# 5_Motor_Driver_Schematic.net
KiCad netlist of a schematic drawn in Altium Designer
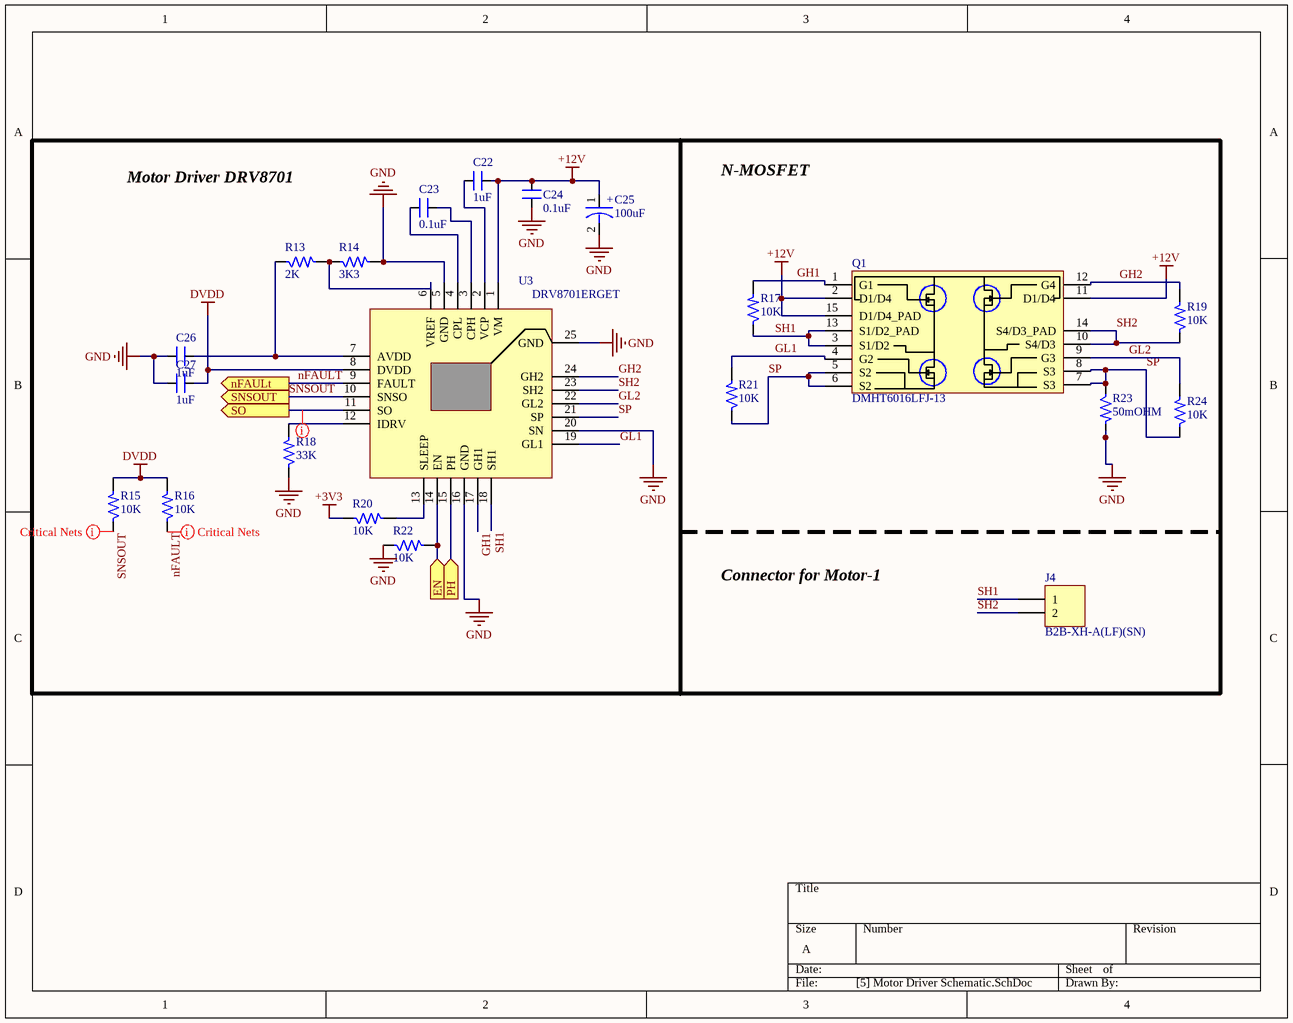
[diagram p0: [5] Motor Driver Schematic.SchDoc]

(export (version "E")
  (design (tool "Eeschema 10.0.6"))
  (components
    (comp (ref "C22")
      (value "1uF")
      (footprint "CAP_0805")
      (description "1µF ±5% 50V Ceramic Capacitor X7R 0805 (2012 Metric)")
      (fields
        (field (name "MANUFACTURER") "Samsung")
        (field (name "MANUFACTURER PART NUMBER") "CC0805JKX7R9BB105")
      )
      (libsource (lib "ESTEEMPCBLIB") (part "CAP_1uF-50V-5%-0805"))
    )
    (comp (ref "C23")
      (value "0.1uF")
      (footprint "CAP_0805")
      (description "0.1µF ±10% 50V Ceramic Capacitor X7R 0805 (2012 Metric)")
      (fields
        (field (name "MANUFACTURER") "Samsung")
        (field (name "MANUFACTURER PART NUMBER") "CL21B104KBCNNNC")
      )
      (libsource (lib "ESTEEMPCBLIB") (part "CAP_0.1uF-50V-10%-0805"))
    )
    (comp (ref "C24")
      (value "0.1uF")
      (footprint "CAP_0805")
      (description "0.1µF ±10% 50V Ceramic Capacitor X7R 0805 (2012 Metric)")
      (fields
        (field (name "MANUFACTURER") "Samsung")
        (field (name "MANUFACTURER PART NUMBER") "CL21B104KBCNNNC")
      )
      (libsource (lib "ESTEEMPCBLIB") (part "CAP_0.1uF-50V-10%-0805"))
    )
    (comp (ref "C25")
      (value "100uF")
      (footprint "ACAP_P236_D305_H303_RAD")
      (description "100µF 25V Aluminum Electrolytic Capacitors Radial, Can - SMD 1000 Hrs @ 105°C")
      (fields
        (field (name "MANUFACTURER") "Nichicon")
        (field (name "MANUFACTURER PART NUMBER") "UWT1E101MCL1GS")
      )
      (libsource (lib "ESTEEMPCBLIB") (part "CAP-P_100uF-25V-20%-RAD"))
    )
    (comp (ref "C26")
      (value "1uF")
      (footprint "CAP_0805")
      (description "1µF ±5% 50V Ceramic Capacitor X7R 0805 (2012 Metric)")
      (fields
        (field (name "MANUFACTURER") "Samsung")
        (field (name "MANUFACTURER PART NUMBER") "CC0805JKX7R9BB105")
      )
      (libsource (lib "ESTEEMPCBLIB") (part "CAP_1uF-50V-5%-0805"))
    )
    (comp (ref "C27")
      (value "1uF")
      (footprint "CAP_0805")
      (description "1µF ±5% 50V Ceramic Capacitor X7R 0805 (2012 Metric)")
      (fields
        (field (name "MANUFACTURER") "Samsung")
        (field (name "MANUFACTURER PART NUMBER") "CC0805JKX7R9BB105")
      )
      (libsource (lib "ESTEEMPCBLIB") (part "CAP_1uF-50V-5%-0805"))
    )
    (comp (ref "J4")
      (value "B2B-XH-A(LF)(SN)")
      (footprint "CON2_100_B2B-XH-A_TH_ST")
      (description "2 Pins, 1 Row 2.54mm Pitch, Straight Connector, male")
      (fields (field (name "MANUFACTURER") "JST") (field (name "MATING PART NUMBER") "XHP-2"))
      (libsource (lib "ESTEEMPCBLIB") (part "CON-PLG_2X1-100-ST-TH"))
    )
    (comp (ref "Q1")
      (value "DMHT6016LFJ-13")
      (footprint "DFN5045-12_33_212_27X15_SMD_1")
      (description "Mosfet Array 4 N-Channel 14.8A (Ta) Surface Mount V-DFN5045-12")
      (fields (field (name "MANUFACTURER") "ON Semiconductor"))
      (libsource (lib "ESTEEMPCBLIB") (part "MOSFET-N_60V-14.8A-V-DFN5045-12"))
    )
    (comp (ref "R13")
      (value "2K")
      (footprint "RES_0603")
      (fields
        (field (name "MANUFACTURER") "Stackpole Electronics")
        (field (name "MANUFACTURER PART NUMBER") "RNCP0603FTD2K00")
      )
      (libsource (lib "ESTEEMPCBLIB") (part "RES_2K-0.125W-1%-0603"))
    )
    (comp (ref "R14")
      (value "3K3")
      (footprint "RES_0603")
      (description "3.3 kOhms ±1% 0.1W, 1/10W Chip Resistor 0603 (1608 Metric) Automotive AEC-Q200 Thick Film")
      (fields (field (name "MANUFACTURER") "Wilson") (field (name "MANUFACTURER PART NUMBER") "WR06X3301FTL"))
      (libsource (lib "ESTEEMPCBLIB") (part "RES_3.3K-0.1W-1%-0603"))
    )
    (comp (ref "R15")
      (value "10K")
      (footprint "RES_0603")
      (description "10 kOhms ±1% 0.1W, 1/10W Chip Resistor 0603 (1608 Metric) Automotive AEC-Q200 Thick Film")
      (fields (field (name "MANUFACTURER") "Walsin") (field (name "MANUFACTURER PART NUMBER") "WR06X1002FTL"))
      (libsource (lib "ESTEEMPCBLIB") (part "RES_10K-0.1W-1%-0603"))
    )
    (comp (ref "R16")
      (value "10K")
      (footprint "RES_0603")
      (description "10 kOhms ±1% 0.1W, 1/10W Chip Resistor 0603 (1608 Metric) Automotive AEC-Q200 Thick Film")
      (fields (field (name "MANUFACTURER") "Walsin") (field (name "MANUFACTURER PART NUMBER") "WR06X1002FTL"))
      (libsource (lib "ESTEEMPCBLIB") (part "RES_10K-0.1W-1%-0603"))
    )
    (comp (ref "R17")
      (value "10K")
      (footprint "RES_0603")
      (description "10 kOhms ±1% 0.1W, 1/10W Chip Resistor 0603 (1608 Metric) Automotive AEC-Q200 Thick Film")
      (fields (field (name "MANUFACTURER") "Walsin") (field (name "MANUFACTURER PART NUMBER") "WR06X1002FTL"))
      (libsource (lib "ESTEEMPCBLIB") (part "RES_10K-0.1W-1%-0603"))
    )
    (comp (ref "R18")
      (value "33K")
      (footprint "RES_0805")
      (fields
        (field (name "MANUFACTURER") "Vishay BCcomponents")
        (field (name "MANUFACTURER PART NUMBER") "CRG0805F33K")
      )
      (libsource (lib "ESTEEMPCBLIB") (part "RES_33K-0.125W-1%-0805"))
    )
    (comp (ref "R19")
      (value "10K")
      (footprint "RES_0603")
      (description "10 kOhms ±1% 0.1W, 1/10W Chip Resistor 0603 (1608 Metric) Automotive AEC-Q200 Thick Film")
      (fields (field (name "MANUFACTURER") "Walsin") (field (name "MANUFACTURER PART NUMBER") "WR06X1002FTL"))
      (libsource (lib "ESTEEMPCBLIB") (part "RES_10K-0.1W-1%-0603"))
    )
    (comp (ref "R20")
      (value "10K")
      (footprint "RES_0603")
      (description "10 kOhms ±1% 0.1W, 1/10W Chip Resistor 0603 (1608 Metric) Automotive AEC-Q200 Thick Film")
      (fields (field (name "MANUFACTURER") "Walsin") (field (name "MANUFACTURER PART NUMBER") "WR06X1002FTL"))
      (libsource (lib "ESTEEMPCBLIB") (part "RES_10K-0.1W-1%-0603"))
    )
    (comp (ref "R21")
      (value "10K")
      (footprint "RES_0603")
      (description "10 kOhms ±1% 0.1W, 1/10W Chip Resistor 0603 (1608 Metric) Automotive AEC-Q200 Thick Film")
      (fields (field (name "MANUFACTURER") "Walsin") (field (name "MANUFACTURER PART NUMBER") "WR06X1002FTL"))
      (libsource (lib "ESTEEMPCBLIB") (part "RES_10K-0.1W-1%-0603"))
    )
    (comp (ref "R22")
      (value "10K")
      (footprint "RES_0603")
      (description "10 kOhms ±1% 0.1W, 1/10W Chip Resistor 0603 (1608 Metric) Automotive AEC-Q200 Thick Film")
      (fields (field (name "MANUFACTURER") "Walsin") (field (name "MANUFACTURER PART NUMBER") "WR06X1002FTL"))
      (libsource (lib "ESTEEMPCBLIB") (part "RES_10K-0.1W-1%-0603"))
    )
    (comp (ref "R23")
      (value "50mOHM")
      (footprint "RES_2512")
      (fields
        (field (name "MANUFACTURER") "Yageo")
        (field (name "MANUFACTURER PART NUMBER") "PA2512FKF7W0R05E")
      )
      (libsource (lib "ESTEEMPCBLIB") (part "RES_50mOhm-2W-1%-2512"))
    )
    (comp (ref "R24")
      (value "10K")
      (footprint "RES_0603")
      (description "10 kOhms ±1% 0.1W, 1/10W Chip Resistor 0603 (1608 Metric) Automotive AEC-Q200 Thick Film")
      (fields (field (name "MANUFACTURER") "Walsin") (field (name "MANUFACTURER PART NUMBER") "WR06X1002FTL"))
      (libsource (lib "ESTEEMPCBLIB") (part "RES_10K-0.1W-1%-0603"))
    )
    (comp (ref "U3")
      (value "DRV8701ERGET")
      (footprint "VFQFN24_19.6_196_12X32_SMD_1")
      (description "Motor Driver Power MOSFET Parallel 24-VQFN (4x4)")
      (fields (field (name "MANUFACTURER") "Texas Instruments"))
      (libsource (lib "ESTEEMPCBLIB") (part "IC_DRV8701ERGET"))
    )
  )
  (nets
    (net (code "1") (name "+3V3") (class "Default")
      (node (ref "R20") (pin "1") (pinfunction "1_1") (pintype "passive"))
    )
    (net (code "2") (name "+12V") (class "Default")
      (node (ref "C22") (pin "1") (pinfunction "1_1") (pintype "passive"))
      (node (ref "C24") (pin "2") (pinfunction "2_2") (pintype "passive"))
      (node (ref "C25") (pin "1") (pinfunction "1_1") (pintype "passive"))
      (node (ref "Q1") (pin "11") (pinfunction "D1/D4_11") (pintype "passive"))
      (node (ref "Q1") (pin "15") (pinfunction "D1/D4_PAD_15") (pintype "passive"))
      (node (ref "Q1") (pin "2") (pinfunction "D1/D4_2") (pintype "passive"))
      (node (ref "U3") (pin "1") (pinfunction "VM_1") (pintype "passive"))
    )
    (net (code "3") (name "/EN") (class "Default")
      (node (ref "R22") (pin "2") (pinfunction "2_2") (pintype "passive"))
      (node (ref "U3") (pin "14") (pinfunction "EN_14") (pintype "passive"))
    )
    (net (code "4") (name "/GH1") (class "Default")
      (node (ref "Q1") (pin "1") (pinfunction "G1_1") (pintype "passive"))
      (node (ref "R17") (pin "2") (pinfunction "2_2") (pintype "passive"))
      (node (ref "U3") (pin "17") (pinfunction "GH1_17") (pintype "passive"))
    )
    (net (code "5") (name "/GH2") (class "Default")
      (node (ref "Q1") (pin "12") (pinfunction "G4_12") (pintype "passive"))
      (node (ref "R19") (pin "2") (pinfunction "2_2") (pintype "passive"))
      (node (ref "U3") (pin "24") (pinfunction "GH2_24") (pintype "passive"))
    )
    (net (code "6") (name "/GL1") (class "Default")
      (node (ref "Q1") (pin "4") (pinfunction "G2_4") (pintype "passive"))
      (node (ref "R21") (pin "2") (pinfunction "2_2") (pintype "passive"))
      (node (ref "U3") (pin "19") (pinfunction "GL1_19") (pintype "passive"))
    )
    (net (code "7") (name "/GL2") (class "Default")
      (node (ref "Q1") (pin "9") (pinfunction "G3_9") (pintype "passive"))
      (node (ref "R24") (pin "2") (pinfunction "2_2") (pintype "passive"))
      (node (ref "U3") (pin "22") (pinfunction "GL2_22") (pintype "passive"))
    )
    (net (code "8") (name "/PH") (class "Default")
      (node (ref "U3") (pin "15") (pinfunction "PH_15") (pintype "passive"))
    )
    (net (code "9") (name "/SH1") (class "Default")
      (node (ref "J4") (pin "1") (pinfunction "1_1") (pintype "passive"))
      (node (ref "Q1") (pin "13") (pinfunction "S1/D2_PAD_13") (pintype "passive"))
      (node (ref "Q1") (pin "3") (pinfunction "S1/D2_3") (pintype "passive"))
      (node (ref "R17") (pin "1") (pinfunction "1_1") (pintype "passive"))
      (node (ref "U3") (pin "18") (pinfunction "SH1_18") (pintype "passive"))
    )
    (net (code "10") (name "/SH2") (class "Default")
      (node (ref "J4") (pin "2") (pinfunction "2_2") (pintype "passive"))
      (node (ref "Q1") (pin "10") (pinfunction "S4/D3_10") (pintype "passive"))
      (node (ref "Q1") (pin "14") (pinfunction "S4/D3_PAD_14") (pintype "passive"))
      (node (ref "R19") (pin "1") (pinfunction "1_1") (pintype "passive"))
      (node (ref "U3") (pin "23") (pinfunction "SH2_23") (pintype "passive"))
    )
    (net (code "11") (name "/SNSOUT") (class "Default")
      (node (ref "R15") (pin "1") (pinfunction "1_1") (pintype "passive"))
      (node (ref "U3") (pin "10") (pinfunction "SNSO_10") (pintype "passive"))
    )
    (net (code "12") (name "/SO") (class "Default")
      (node (ref "U3") (pin "11") (pinfunction "SO_11") (pintype "passive"))
    )
    (net (code "13") (name "/SP") (class "Default")
      (node (ref "Q1") (pin "5") (pinfunction "S2_5") (pintype "passive"))
      (node (ref "Q1") (pin "6") (pinfunction "S2_6") (pintype "passive"))
      (node (ref "Q1") (pin "7") (pinfunction "S3_7") (pintype "passive"))
      (node (ref "Q1") (pin "8") (pinfunction "S3_8") (pintype "passive"))
      (node (ref "R21") (pin "1") (pinfunction "1_1") (pintype "passive"))
      (node (ref "R23") (pin "1") (pinfunction "1_1") (pintype "passive"))
      (node (ref "R24") (pin "1") (pinfunction "1_1") (pintype "passive"))
      (node (ref "U3") (pin "21") (pinfunction "SP_21") (pintype "passive"))
    )
    (net (code "14") (name "/nFAULT") (class "Default")
      (node (ref "R16") (pin "1") (pinfunction "1_1") (pintype "passive"))
      (node (ref "U3") (pin "9") (pinfunction "FAULT_9") (pintype "passive"))
    )
    (net (code "15") (name "DVDD") (class "Default")
      (node (ref "C27") (pin "2") (pinfunction "2_2") (pintype "passive"))
      (node (ref "R15") (pin "2") (pinfunction "2_2") (pintype "passive"))
      (node (ref "R16") (pin "2") (pinfunction "2_2") (pintype "passive"))
      (node (ref "U3") (pin "8") (pinfunction "DVDD_8") (pintype "passive"))
    )
    (net (code "16") (name "GND") (class "Default")
      (node (ref "C24") (pin "1") (pinfunction "1_1") (pintype "passive"))
      (node (ref "C25") (pin "2") (pinfunction "2_2") (pintype "passive"))
      (node (ref "C26") (pin "1") (pinfunction "1_1") (pintype "passive"))
      (node (ref "C27") (pin "1") (pinfunction "1_1") (pintype "passive"))
      (node (ref "R14") (pin "2") (pinfunction "2_2") (pintype "passive"))
      (node (ref "R18") (pin "1") (pinfunction "1_1") (pintype "passive"))
      (node (ref "R22") (pin "1") (pinfunction "1_1") (pintype "passive"))
      (node (ref "R23") (pin "2") (pinfunction "2_2") (pintype "passive"))
      (node (ref "U3") (pin "16") (pinfunction "GND_16") (pintype "passive"))
      (node (ref "U3") (pin "20") (pinfunction "SN_20") (pintype "passive"))
      (node (ref "U3") (pin "25") (pinfunction "GND_25") (pintype "passive"))
      (node (ref "U3") (pin "5") (pinfunction "GND_5") (pintype "passive"))
    )
    (net (code "17") (name "Net-(U3-AVDD)") (class "Default")
      (node (ref "C26") (pin "2") (pinfunction "2_2") (pintype "passive"))
      (node (ref "R13") (pin "1") (pinfunction "1_1") (pintype "passive"))
      (node (ref "U3") (pin "7") (pinfunction "AVDD_7") (pintype "passive"))
    )
    (net (code "18") (name "Net-(U3-CPH)") (class "Default")
      (node (ref "C23") (pin "1") (pinfunction "1_1") (pintype "passive"))
      (node (ref "U3") (pin "3") (pinfunction "CPH_3") (pintype "passive"))
    )
    (net (code "19") (name "Net-(U3-CPL)") (class "Default")
      (node (ref "C23") (pin "2") (pinfunction "2_2") (pintype "passive"))
      (node (ref "U3") (pin "4") (pinfunction "CPL_4") (pintype "passive"))
    )
    (net (code "20") (name "Net-(U3-IDRV)") (class "Default")
      (node (ref "R18") (pin "2") (pinfunction "2_2") (pintype "passive"))
      (node (ref "U3") (pin "12") (pinfunction "IDRV_12") (pintype "passive"))
    )
    (net (code "21") (name "Net-(U3-SLEEP)") (class "Default")
      (node (ref "R20") (pin "2") (pinfunction "2_2") (pintype "passive"))
      (node (ref "U3") (pin "13") (pinfunction "SLEEP_13") (pintype "passive"))
    )
    (net (code "22") (name "Net-(U3-VCP)") (class "Default")
      (node (ref "C22") (pin "2") (pinfunction "2_2") (pintype "passive"))
      (node (ref "U3") (pin "2") (pinfunction "VCP_2") (pintype "passive"))
    )
    (net (code "23") (name "Net-(U3-VREF)") (class "Default")
      (node (ref "R13") (pin "2") (pinfunction "2_2") (pintype "passive"))
      (node (ref "R14") (pin "1") (pinfunction "1_1") (pintype "passive"))
      (node (ref "U3") (pin "6") (pinfunction "VREF_6") (pintype "passive"))
    )
  )
)
